# Photogate1.net
KiCad netlist of a schematic drawn in EasyEDA
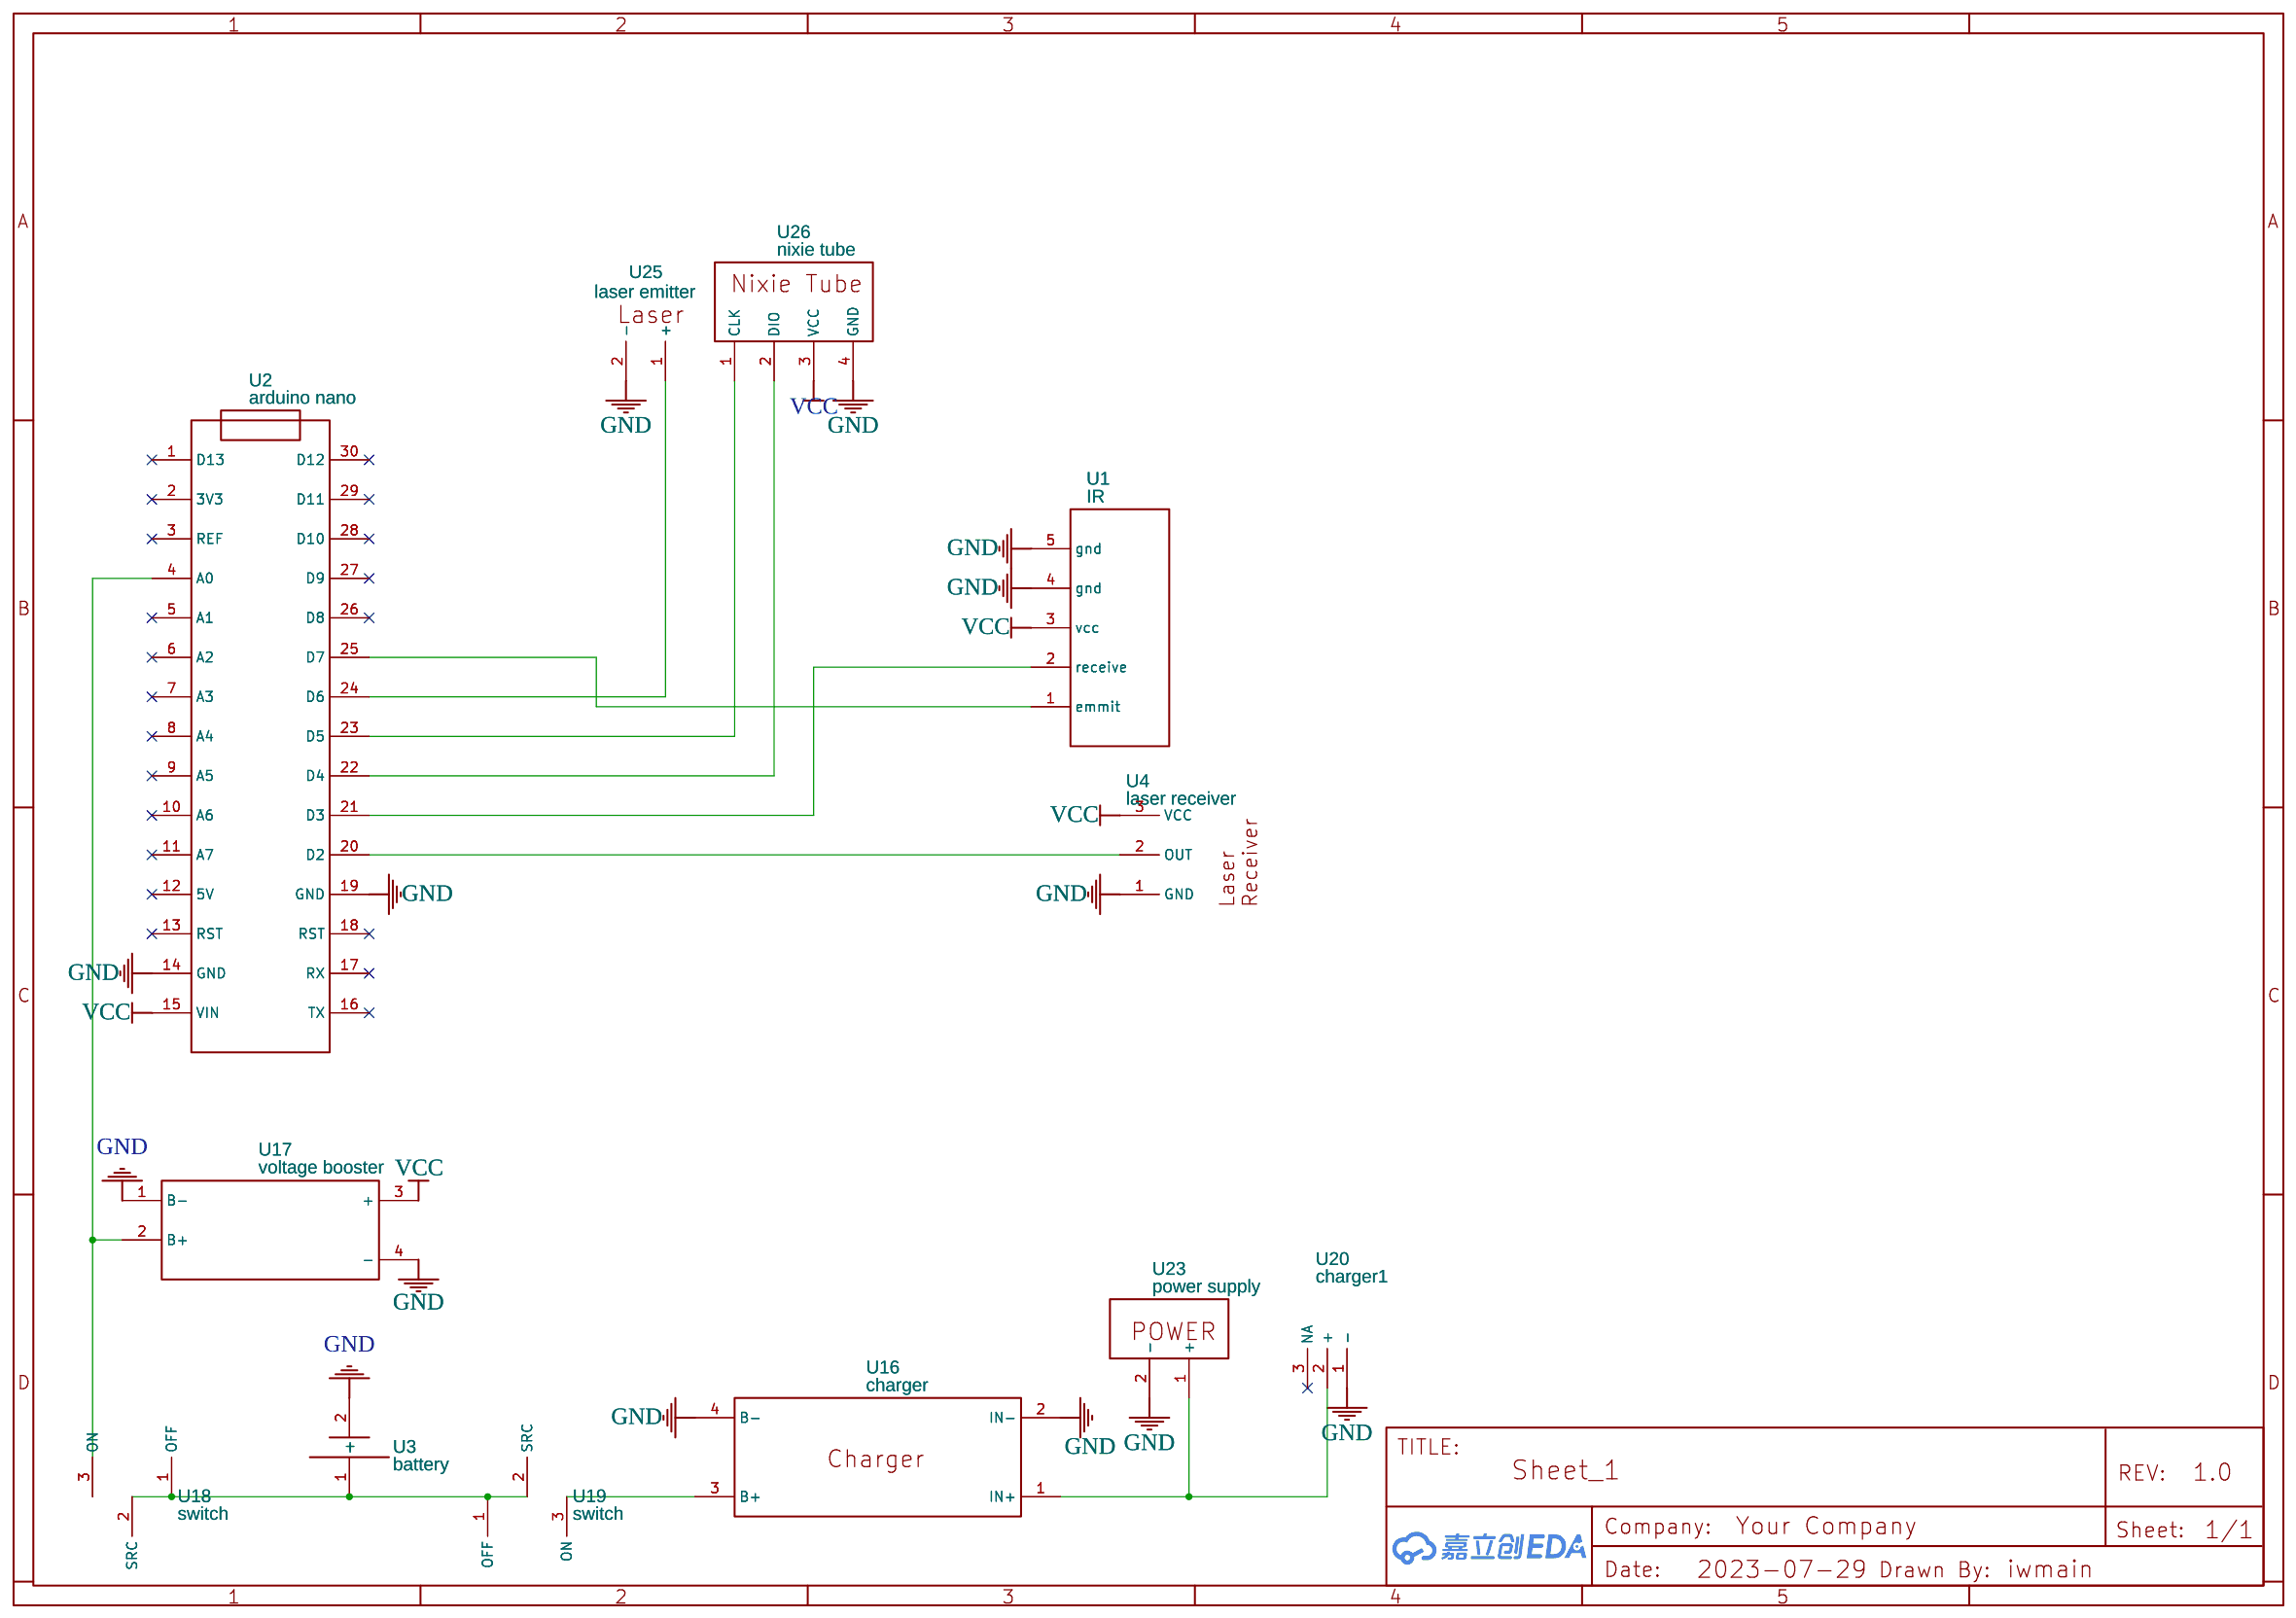
[diagram p0: schematic sheet]

(export (version "E")
  (design (tool "Eeschema 10.0.6"))
  (components
    (comp (ref "U1") (value "IR") (libsource (lib "") (part "IR")))
    (comp (ref "U2") (value "arduino nano") (libsource (lib "") (part "arduino nano")))
    (comp (ref "U3") (value "battery") (libsource (lib "") (part "battery")))
    (comp (ref "U4") (value "laser receiver") (libsource (lib "") (part "laser receiver")))
    (comp (ref "U16") (value "charger") (libsource (lib "") (part "charger")))
    (comp (ref "U17") (value "voltage booster") (libsource (lib "") (part "voltage booster")))
    (comp (ref "U18") (value "switch") (libsource (lib "") (part "switch_1")))
    (comp (ref "U19") (value "switch") (libsource (lib "") (part "switch")))
    (comp (ref "U20") (value "charger1") (libsource (lib "") (part "charger1")))
    (comp (ref "U23") (value "power supply") (libsource (lib "") (part "power supply")))
    (comp (ref "U25") (value "laser emitter") (libsource (lib "") (part "laser emitter")))
    (comp (ref "U26") (value "nixie tube") (libsource (lib "") (part "nixie tube")))
  )
  (nets
    (net (code "1") (name "GND") (class "Default")
      (node (ref "U1") (pin "4") (pinfunction "gnd_4") (pintype "unspecified"))
      (node (ref "U1") (pin "5") (pinfunction "gnd_5") (pintype "unspecified"))
      (node (ref "U16") (pin "2") (pinfunction "IN-_2") (pintype "unspecified"))
      (node (ref "U16") (pin "4") (pinfunction "B-_4") (pintype "unspecified"))
      (node (ref "U17") (pin "1") (pinfunction "B-_1") (pintype "unspecified"))
      (node (ref "U17") (pin "4") (pinfunction "-_4") (pintype "unspecified"))
      (node (ref "U2") (pin "14") (pinfunction "GND_14") (pintype "unspecified"))
      (node (ref "U2") (pin "19") (pinfunction "GND_19") (pintype "unspecified"))
      (node (ref "U20") (pin "1") (pinfunction "-_1") (pintype "unspecified"))
      (node (ref "U23") (pin "2") (pinfunction "-_2") (pintype "unspecified"))
      (node (ref "U25") (pin "2") (pinfunction "-_2") (pintype "unspecified"))
      (node (ref "U26") (pin "4") (pinfunction "GND_4") (pintype "unspecified"))
      (node (ref "U3") (pin "2") (pinfunction "-_2") (pintype "unspecified"))
      (node (ref "U4") (pin "1") (pinfunction "GND_1") (pintype "unspecified"))
    )
    (net (code "2") (name "Net-(U1-emmit)") (class "Default")
      (node (ref "U1") (pin "1") (pinfunction "emmit_1") (pintype "unspecified"))
      (node (ref "U2") (pin "25") (pinfunction "D7_25") (pintype "unspecified"))
    )
    (net (code "3") (name "Net-(U1-receive)") (class "Default")
      (node (ref "U1") (pin "2") (pinfunction "receive_2") (pintype "unspecified"))
      (node (ref "U2") (pin "21") (pinfunction "D3_21") (pintype "unspecified"))
    )
    (net (code "4") (name "Net-(U2-D2)") (class "Default")
      (node (ref "U2") (pin "20") (pinfunction "D2_20") (pintype "unspecified"))
      (node (ref "U4") (pin "2") (pinfunction "OUT_2") (pintype "unspecified"))
    )
    (net (code "5") (name "Net-(U2-D4)") (class "Default")
      (node (ref "U2") (pin "22") (pinfunction "D4_22") (pintype "unspecified"))
      (node (ref "U26") (pin "2") (pinfunction "DIO_2") (pintype "unspecified"))
    )
    (net (code "6") (name "Net-(U2-D5)") (class "Default")
      (node (ref "U2") (pin "23") (pinfunction "D5_23") (pintype "unspecified"))
      (node (ref "U26") (pin "1") (pinfunction "CLK_1") (pintype "unspecified"))
    )
    (net (code "7") (name "Net-(U2-D6)") (class "Default")
      (node (ref "U2") (pin "24") (pinfunction "D6_24") (pintype "unspecified"))
      (node (ref "U25") (pin "1") (pinfunction "+_1") (pintype "unspecified"))
    )
    (net (code "8") (name "Net-(U16-B+)") (class "Default")
      (node (ref "U16") (pin "3") (pinfunction "B+_3") (pintype "unspecified"))
      (node (ref "U19") (pin "3") (pinfunction "ON_3") (pintype "unspecified"))
    )
    (net (code "9") (name "Net-(U16-IN+)") (class "Default")
      (node (ref "U16") (pin "1") (pinfunction "IN+_1") (pintype "unspecified"))
      (node (ref "U20") (pin "2") (pinfunction "+_2") (pintype "unspecified"))
      (node (ref "U23") (pin "1") (pinfunction "+_1") (pintype "unspecified"))
    )
    (net (code "10") (name "Net-(U17-B+)") (class "Default")
      (node (ref "U17") (pin "2") (pinfunction "B+_2") (pintype "unspecified"))
      (node (ref "U18") (pin "3") (pinfunction "ON_3") (pintype "unspecified"))
      (node (ref "U2") (pin "4") (pinfunction "A0_4") (pintype "unspecified"))
    )
    (net (code "11") (name "Net-(U18-OFF)") (class "Default")
      (node (ref "U18") (pin "1") (pinfunction "OFF_1") (pintype "unspecified"))
      (node (ref "U18") (pin "2") (pinfunction "SRC_2") (pintype "unspecified"))
      (node (ref "U19") (pin "1") (pinfunction "OFF_1") (pintype "unspecified"))
      (node (ref "U19") (pin "2") (pinfunction "SRC_2") (pintype "unspecified"))
      (node (ref "U3") (pin "1") (pinfunction "+_1") (pintype "unspecified"))
    )
    (net (code "12") (name "VCC") (class "Default")
      (node (ref "U1") (pin "3") (pinfunction "vcc_3") (pintype "unspecified"))
      (node (ref "U17") (pin "3") (pinfunction "+_3") (pintype "unspecified"))
      (node (ref "U2") (pin "15") (pinfunction "VIN_15") (pintype "unspecified"))
      (node (ref "U26") (pin "3") (pinfunction "VCC_3") (pintype "unspecified"))
      (node (ref "U4") (pin "3") (pinfunction "VCC_3") (pintype "unspecified"))
    )
    (net (code "13") (name "unconnected-(U2-3V3-Pad2)") (class "Default")
      (node (ref "U2") (pin "2") (pinfunction "3V3_2") (pintype "unspecified+no_connect"))
    )
    (net (code "14") (name "unconnected-(U2-5V-Pad12)") (class "Default")
      (node (ref "U2") (pin "12") (pinfunction "5V_12") (pintype "unspecified+no_connect"))
    )
    (net (code "15") (name "unconnected-(U2-A1-Pad5)") (class "Default")
      (node (ref "U2") (pin "5") (pinfunction "A1_5") (pintype "unspecified+no_connect"))
    )
    (net (code "16") (name "unconnected-(U2-A2-Pad6)") (class "Default")
      (node (ref "U2") (pin "6") (pinfunction "A2_6") (pintype "unspecified+no_connect"))
    )
    (net (code "17") (name "unconnected-(U2-A3-Pad7)") (class "Default")
      (node (ref "U2") (pin "7") (pinfunction "A3_7") (pintype "unspecified+no_connect"))
    )
    (net (code "18") (name "unconnected-(U2-A4-Pad8)") (class "Default")
      (node (ref "U2") (pin "8") (pinfunction "A4_8") (pintype "unspecified+no_connect"))
    )
    (net (code "19") (name "unconnected-(U2-A5-Pad9)") (class "Default")
      (node (ref "U2") (pin "9") (pinfunction "A5_9") (pintype "unspecified+no_connect"))
    )
    (net (code "20") (name "unconnected-(U2-A6-Pad10)") (class "Default")
      (node (ref "U2") (pin "10") (pinfunction "A6_10") (pintype "unspecified+no_connect"))
    )
    (net (code "21") (name "unconnected-(U2-A7-Pad11)") (class "Default")
      (node (ref "U2") (pin "11") (pinfunction "A7_11") (pintype "unspecified+no_connect"))
    )
    (net (code "22") (name "unconnected-(U2-D8-Pad26)") (class "Default")
      (node (ref "U2") (pin "26") (pinfunction "D8_26") (pintype "unspecified+no_connect"))
    )
    (net (code "23") (name "unconnected-(U2-D9-Pad27)") (class "Default")
      (node (ref "U2") (pin "27") (pinfunction "D9_27") (pintype "unspecified+no_connect"))
    )
    (net (code "24") (name "unconnected-(U2-D10-Pad28)") (class "Default")
      (node (ref "U2") (pin "28") (pinfunction "D10_28") (pintype "unspecified+no_connect"))
    )
    (net (code "25") (name "unconnected-(U2-D11-Pad29)") (class "Default")
      (node (ref "U2") (pin "29") (pinfunction "D11_29") (pintype "unspecified+no_connect"))
    )
    (net (code "26") (name "unconnected-(U2-D12-Pad30)") (class "Default")
      (node (ref "U2") (pin "30") (pinfunction "D12_30") (pintype "unspecified+no_connect"))
    )
    (net (code "27") (name "unconnected-(U2-D13-Pad1)") (class "Default")
      (node (ref "U2") (pin "1") (pinfunction "D13_1") (pintype "unspecified+no_connect"))
    )
    (net (code "28") (name "unconnected-(U2-REF-Pad3)") (class "Default")
      (node (ref "U2") (pin "3") (pinfunction "REF_3") (pintype "unspecified+no_connect"))
    )
    (net (code "29") (name "unconnected-(U2-RST-Pad13)") (class "Default")
      (node (ref "U2") (pin "13") (pinfunction "RST_13") (pintype "unspecified+no_connect"))
    )
    (net (code "30") (name "unconnected-(U2-RST-Pad18)") (class "Default")
      (node (ref "U2") (pin "18") (pinfunction "RST_18") (pintype "unspecified+no_connect"))
    )
    (net (code "31") (name "unconnected-(U2-RX-Pad17)") (class "Default")
      (node (ref "U2") (pin "17") (pinfunction "RX_17") (pintype "unspecified+no_connect"))
    )
    (net (code "32") (name "unconnected-(U2-TX-Pad16)") (class "Default")
      (node (ref "U2") (pin "16") (pinfunction "TX_16") (pintype "unspecified+no_connect"))
    )
    (net (code "33") (name "unconnected-(U20-NA-Pad3)") (class "Default")
      (node (ref "U20") (pin "3") (pinfunction "NA_3") (pintype "unspecified+no_connect"))
    )
  )
)
